# Connectors.net
KiCad netlist of a schematic drawn in Altium Designer
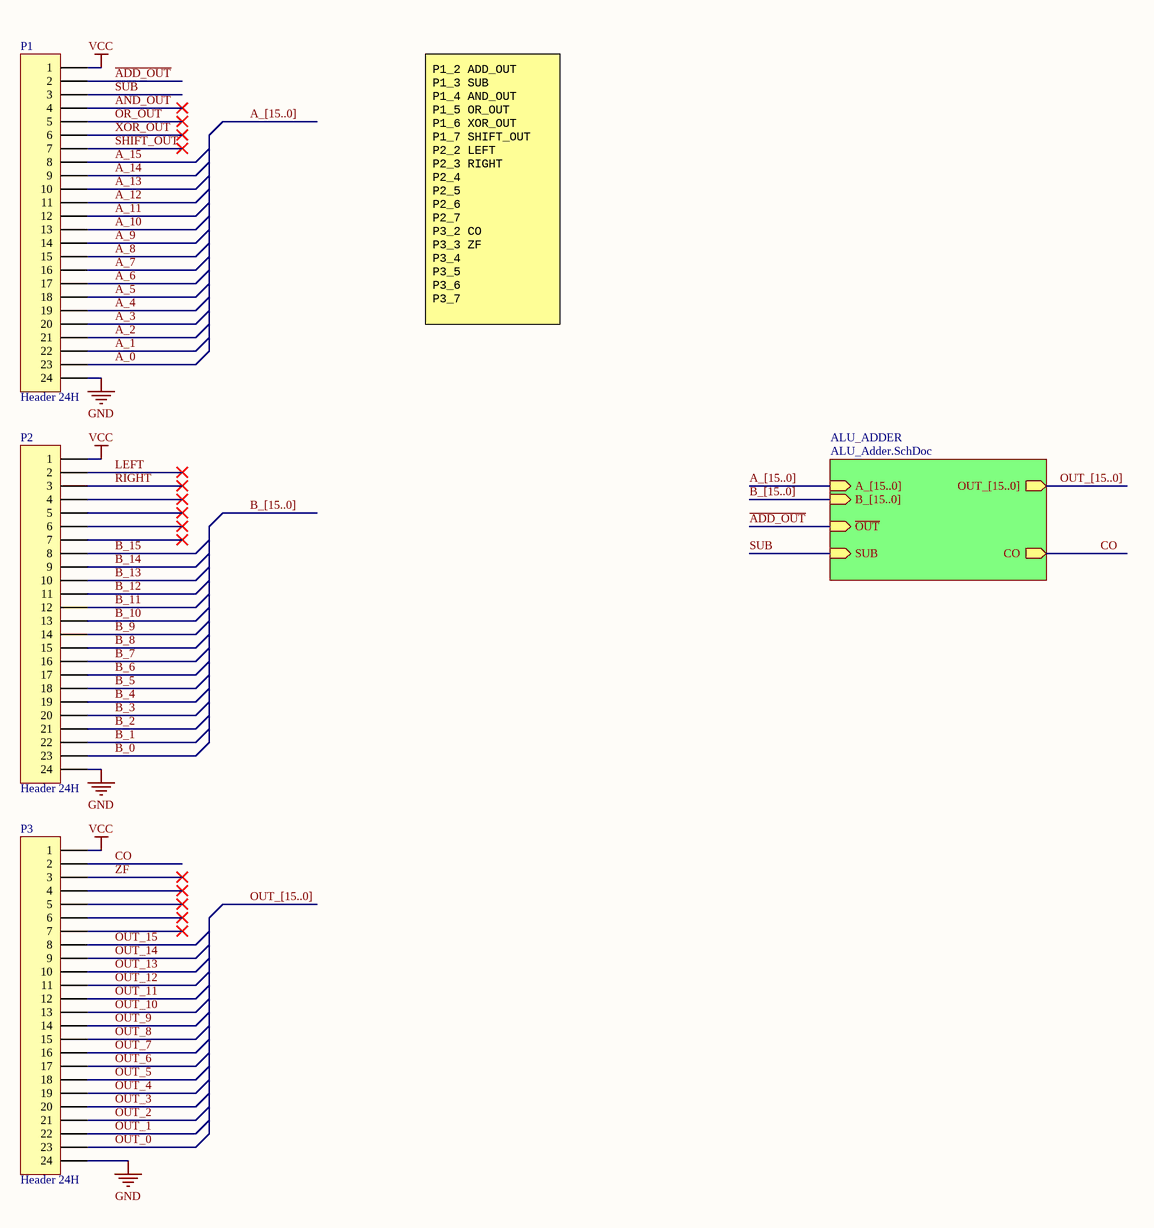
[diagram p0: Connectors.SchDoc]

(export (version "E")
  (design (tool "Eeschema 10.0.6"))
  (components
    (comp (ref "P1")
      (value "Header 24H")
      (footprint "HDR1X24H")
      (description "Header, 24-Pin, Right Angle")
      (fields (field (name "PUBLISHER") "Altium Limited"))
      (libsource (lib "Miscellaneous Connectors") (part "Header 24H"))
    )
    (comp (ref "P2")
      (value "Header 24H")
      (footprint "HDR1X24H")
      (description "Header, 24-Pin, Right Angle")
      (fields (field (name "PUBLISHER") "Altium Limited"))
      (libsource (lib "Miscellaneous Connectors") (part "Header 24H"))
    )
    (comp (ref "P3")
      (value "Header 24H")
      (footprint "HDR1X24H")
      (description "Header, 24-Pin, Right Angle")
      (fields (field (name "PUBLISHER") "Altium Limited"))
      (libsource (lib "Miscellaneous Connectors") (part "Header 24H"))
    )
  )
  (nets
    (net (code "1") (name "/A_0") (class "Default")
      (node (ref "P1") (pin "23") (pinfunction "23_23") (pintype "passive"))
    )
    (net (code "2") (name "/A_1") (class "Default")
      (node (ref "P1") (pin "22") (pinfunction "22_22") (pintype "passive"))
    )
    (net (code "3") (name "/A_2") (class "Default")
      (node (ref "P1") (pin "21") (pinfunction "21_21") (pintype "passive"))
    )
    (net (code "4") (name "/A_3") (class "Default")
      (node (ref "P1") (pin "20") (pinfunction "20_20") (pintype "passive"))
    )
    (net (code "5") (name "/A_4") (class "Default")
      (node (ref "P1") (pin "19") (pinfunction "19_19") (pintype "passive"))
    )
    (net (code "6") (name "/A_5") (class "Default")
      (node (ref "P1") (pin "18") (pinfunction "18_18") (pintype "passive"))
    )
    (net (code "7") (name "/A_6") (class "Default")
      (node (ref "P1") (pin "17") (pinfunction "17_17") (pintype "passive"))
    )
    (net (code "8") (name "/A_7") (class "Default")
      (node (ref "P1") (pin "16") (pinfunction "16_16") (pintype "passive"))
    )
    (net (code "9") (name "/A_8") (class "Default")
      (node (ref "P1") (pin "15") (pinfunction "15_15") (pintype "passive"))
    )
    (net (code "10") (name "/A_9") (class "Default")
      (node (ref "P1") (pin "14") (pinfunction "14_14") (pintype "passive"))
    )
    (net (code "11") (name "/A_10") (class "Default")
      (node (ref "P1") (pin "13") (pinfunction "13_13") (pintype "passive"))
    )
    (net (code "12") (name "/A_11") (class "Default")
      (node (ref "P1") (pin "12") (pinfunction "12_12") (pintype "passive"))
    )
    (net (code "13") (name "/A_12") (class "Default")
      (node (ref "P1") (pin "11") (pinfunction "11_11") (pintype "passive"))
    )
    (net (code "14") (name "/A_13") (class "Default")
      (node (ref "P1") (pin "10") (pinfunction "10_10") (pintype "passive"))
    )
    (net (code "15") (name "/A_14") (class "Default")
      (node (ref "P1") (pin "9") (pinfunction "9_9") (pintype "passive"))
    )
    (net (code "16") (name "/A_15") (class "Default")
      (node (ref "P1") (pin "8") (pinfunction "8_8") (pintype "passive"))
    )
    (net (code "18") (name "/B_0") (class "Default")
      (node (ref "P2") (pin "23") (pinfunction "23_23") (pintype "passive"))
    )
    (net (code "19") (name "/B_1") (class "Default")
      (node (ref "P2") (pin "22") (pinfunction "22_22") (pintype "passive"))
    )
    (net (code "20") (name "/B_2") (class "Default")
      (node (ref "P2") (pin "21") (pinfunction "21_21") (pintype "passive"))
    )
    (net (code "21") (name "/B_3") (class "Default")
      (node (ref "P2") (pin "20") (pinfunction "20_20") (pintype "passive"))
    )
    (net (code "22") (name "/B_4") (class "Default")
      (node (ref "P2") (pin "19") (pinfunction "19_19") (pintype "passive"))
    )
    (net (code "23") (name "/B_5") (class "Default")
      (node (ref "P2") (pin "18") (pinfunction "18_18") (pintype "passive"))
    )
    (net (code "24") (name "/B_6") (class "Default")
      (node (ref "P2") (pin "17") (pinfunction "17_17") (pintype "passive"))
    )
    (net (code "25") (name "/B_7") (class "Default")
      (node (ref "P2") (pin "16") (pinfunction "16_16") (pintype "passive"))
    )
    (net (code "26") (name "/B_8") (class "Default")
      (node (ref "P2") (pin "15") (pinfunction "15_15") (pintype "passive"))
    )
    (net (code "27") (name "/B_9") (class "Default")
      (node (ref "P2") (pin "14") (pinfunction "14_14") (pintype "passive"))
    )
    (net (code "28") (name "/B_10") (class "Default")
      (node (ref "P2") (pin "13") (pinfunction "13_13") (pintype "passive"))
    )
    (net (code "29") (name "/B_11") (class "Default")
      (node (ref "P2") (pin "12") (pinfunction "12_12") (pintype "passive"))
    )
    (net (code "30") (name "/B_12") (class "Default")
      (node (ref "P2") (pin "11") (pinfunction "11_11") (pintype "passive"))
    )
    (net (code "31") (name "/B_13") (class "Default")
      (node (ref "P2") (pin "10") (pinfunction "10_10") (pintype "passive"))
    )
    (net (code "32") (name "/B_14") (class "Default")
      (node (ref "P2") (pin "9") (pinfunction "9_9") (pintype "passive"))
    )
    (net (code "33") (name "/B_15") (class "Default")
      (node (ref "P2") (pin "8") (pinfunction "8_8") (pintype "passive"))
    )
    (net (code "35") (name "/CO") (class "Default")
      (node (ref "P3") (pin "2") (pinfunction "2_2") (pintype "passive"))
    )
    (net (code "36") (name "/LEFT") (class "Default")
      (node (ref "P2") (pin "2") (pinfunction "2_2") (pintype "passive+no_connect"))
    )
    (net (code "37") (name "/OUT_0") (class "Default")
      (node (ref "P3") (pin "23") (pinfunction "23_23") (pintype "passive"))
    )
    (net (code "38") (name "/OUT_1") (class "Default")
      (node (ref "P3") (pin "22") (pinfunction "22_22") (pintype "passive"))
    )
    (net (code "39") (name "/OUT_2") (class "Default")
      (node (ref "P3") (pin "21") (pinfunction "21_21") (pintype "passive"))
    )
    (net (code "40") (name "/OUT_3") (class "Default")
      (node (ref "P3") (pin "20") (pinfunction "20_20") (pintype "passive"))
    )
    (net (code "41") (name "/OUT_4") (class "Default")
      (node (ref "P3") (pin "19") (pinfunction "19_19") (pintype "passive"))
    )
    (net (code "42") (name "/OUT_5") (class "Default")
      (node (ref "P3") (pin "18") (pinfunction "18_18") (pintype "passive"))
    )
    (net (code "43") (name "/OUT_6") (class "Default")
      (node (ref "P3") (pin "17") (pinfunction "17_17") (pintype "passive"))
    )
    (net (code "44") (name "/OUT_7") (class "Default")
      (node (ref "P3") (pin "16") (pinfunction "16_16") (pintype "passive"))
    )
    (net (code "45") (name "/OUT_8") (class "Default")
      (node (ref "P3") (pin "15") (pinfunction "15_15") (pintype "passive"))
    )
    (net (code "46") (name "/OUT_9") (class "Default")
      (node (ref "P3") (pin "14") (pinfunction "14_14") (pintype "passive"))
    )
    (net (code "47") (name "/OUT_10") (class "Default")
      (node (ref "P3") (pin "13") (pinfunction "13_13") (pintype "passive"))
    )
    (net (code "48") (name "/OUT_11") (class "Default")
      (node (ref "P3") (pin "12") (pinfunction "12_12") (pintype "passive"))
    )
    (net (code "49") (name "/OUT_12") (class "Default")
      (node (ref "P3") (pin "11") (pinfunction "11_11") (pintype "passive"))
    )
    (net (code "50") (name "/OUT_13") (class "Default")
      (node (ref "P3") (pin "10") (pinfunction "10_10") (pintype "passive"))
    )
    (net (code "51") (name "/OUT_14") (class "Default")
      (node (ref "P3") (pin "9") (pinfunction "9_9") (pintype "passive"))
    )
    (net (code "52") (name "/OUT_15") (class "Default")
      (node (ref "P3") (pin "8") (pinfunction "8_8") (pintype "passive"))
    )
    (net (code "54") (name "/RIGHT") (class "Default")
      (node (ref "P2") (pin "3") (pinfunction "3_3") (pintype "passive+no_connect"))
    )
    (net (code "55") (name "/SUB") (class "Default")
      (node (ref "P1") (pin "3") (pinfunction "3_3") (pintype "passive"))
    )
    (net (code "56") (name "/~{ADD_OUT}") (class "Default")
      (node (ref "P1") (pin "2") (pinfunction "2_2") (pintype "passive"))
    )
    (net (code "57") (name "/~{AND_OUT}") (class "Default")
      (node (ref "P1") (pin "4") (pinfunction "4_4") (pintype "passive+no_connect"))
    )
    (net (code "58") (name "/~{OR_OUT}") (class "Default")
      (node (ref "P1") (pin "5") (pinfunction "5_5") (pintype "passive+no_connect"))
    )
    (net (code "59") (name "/~{SHIFT_OUT}") (class "Default")
      (node (ref "P1") (pin "7") (pinfunction "7_7") (pintype "passive+no_connect"))
    )
    (net (code "60") (name "/~{XOR_OUT}") (class "Default")
      (node (ref "P1") (pin "6") (pinfunction "6_6") (pintype "passive+no_connect"))
    )
    (net (code "61") (name "/~{ZF}") (class "Default")
      (node (ref "P3") (pin "3") (pinfunction "3_3") (pintype "passive+no_connect"))
    )
    (net (code "62") (name "GND") (class "Default")
      (node (ref "P1") (pin "24") (pinfunction "24_24") (pintype "passive"))
      (node (ref "P2") (pin "24") (pinfunction "24_24") (pintype "passive"))
      (node (ref "P3") (pin "24") (pinfunction "24_24") (pintype "passive"))
    )
    (net (code "63") (name "VCC") (class "Default")
      (node (ref "P1") (pin "1") (pinfunction "1_1") (pintype "passive"))
      (node (ref "P2") (pin "1") (pinfunction "1_1") (pintype "passive"))
      (node (ref "P3") (pin "1") (pinfunction "1_1") (pintype "passive"))
    )
    (net (code "64") (name "unconnected-(P2-Pad4)") (class "Default")
      (node (ref "P2") (pin "4") (pinfunction "4_4") (pintype "passive+no_connect"))
    )
    (net (code "65") (name "unconnected-(P2-Pad5)") (class "Default")
      (node (ref "P2") (pin "5") (pinfunction "5_5") (pintype "passive+no_connect"))
    )
    (net (code "66") (name "unconnected-(P2-Pad6)") (class "Default")
      (node (ref "P2") (pin "6") (pinfunction "6_6") (pintype "passive+no_connect"))
    )
    (net (code "67") (name "unconnected-(P2-Pad7)") (class "Default")
      (node (ref "P2") (pin "7") (pinfunction "7_7") (pintype "passive+no_connect"))
    )
    (net (code "68") (name "unconnected-(P3-Pad4)") (class "Default")
      (node (ref "P3") (pin "4") (pinfunction "4_4") (pintype "passive+no_connect"))
    )
    (net (code "69") (name "unconnected-(P3-Pad5)") (class "Default")
      (node (ref "P3") (pin "5") (pinfunction "5_5") (pintype "passive+no_connect"))
    )
    (net (code "70") (name "unconnected-(P3-Pad6)") (class "Default")
      (node (ref "P3") (pin "6") (pinfunction "6_6") (pintype "passive+no_connect"))
    )
    (net (code "71") (name "unconnected-(P3-Pad7)") (class "Default")
      (node (ref "P3") (pin "7") (pinfunction "7_7") (pintype "passive+no_connect"))
    )
  )
)
